# 3V3Buck_Converter.net
KiCad netlist of a schematic drawn in Altium Designer
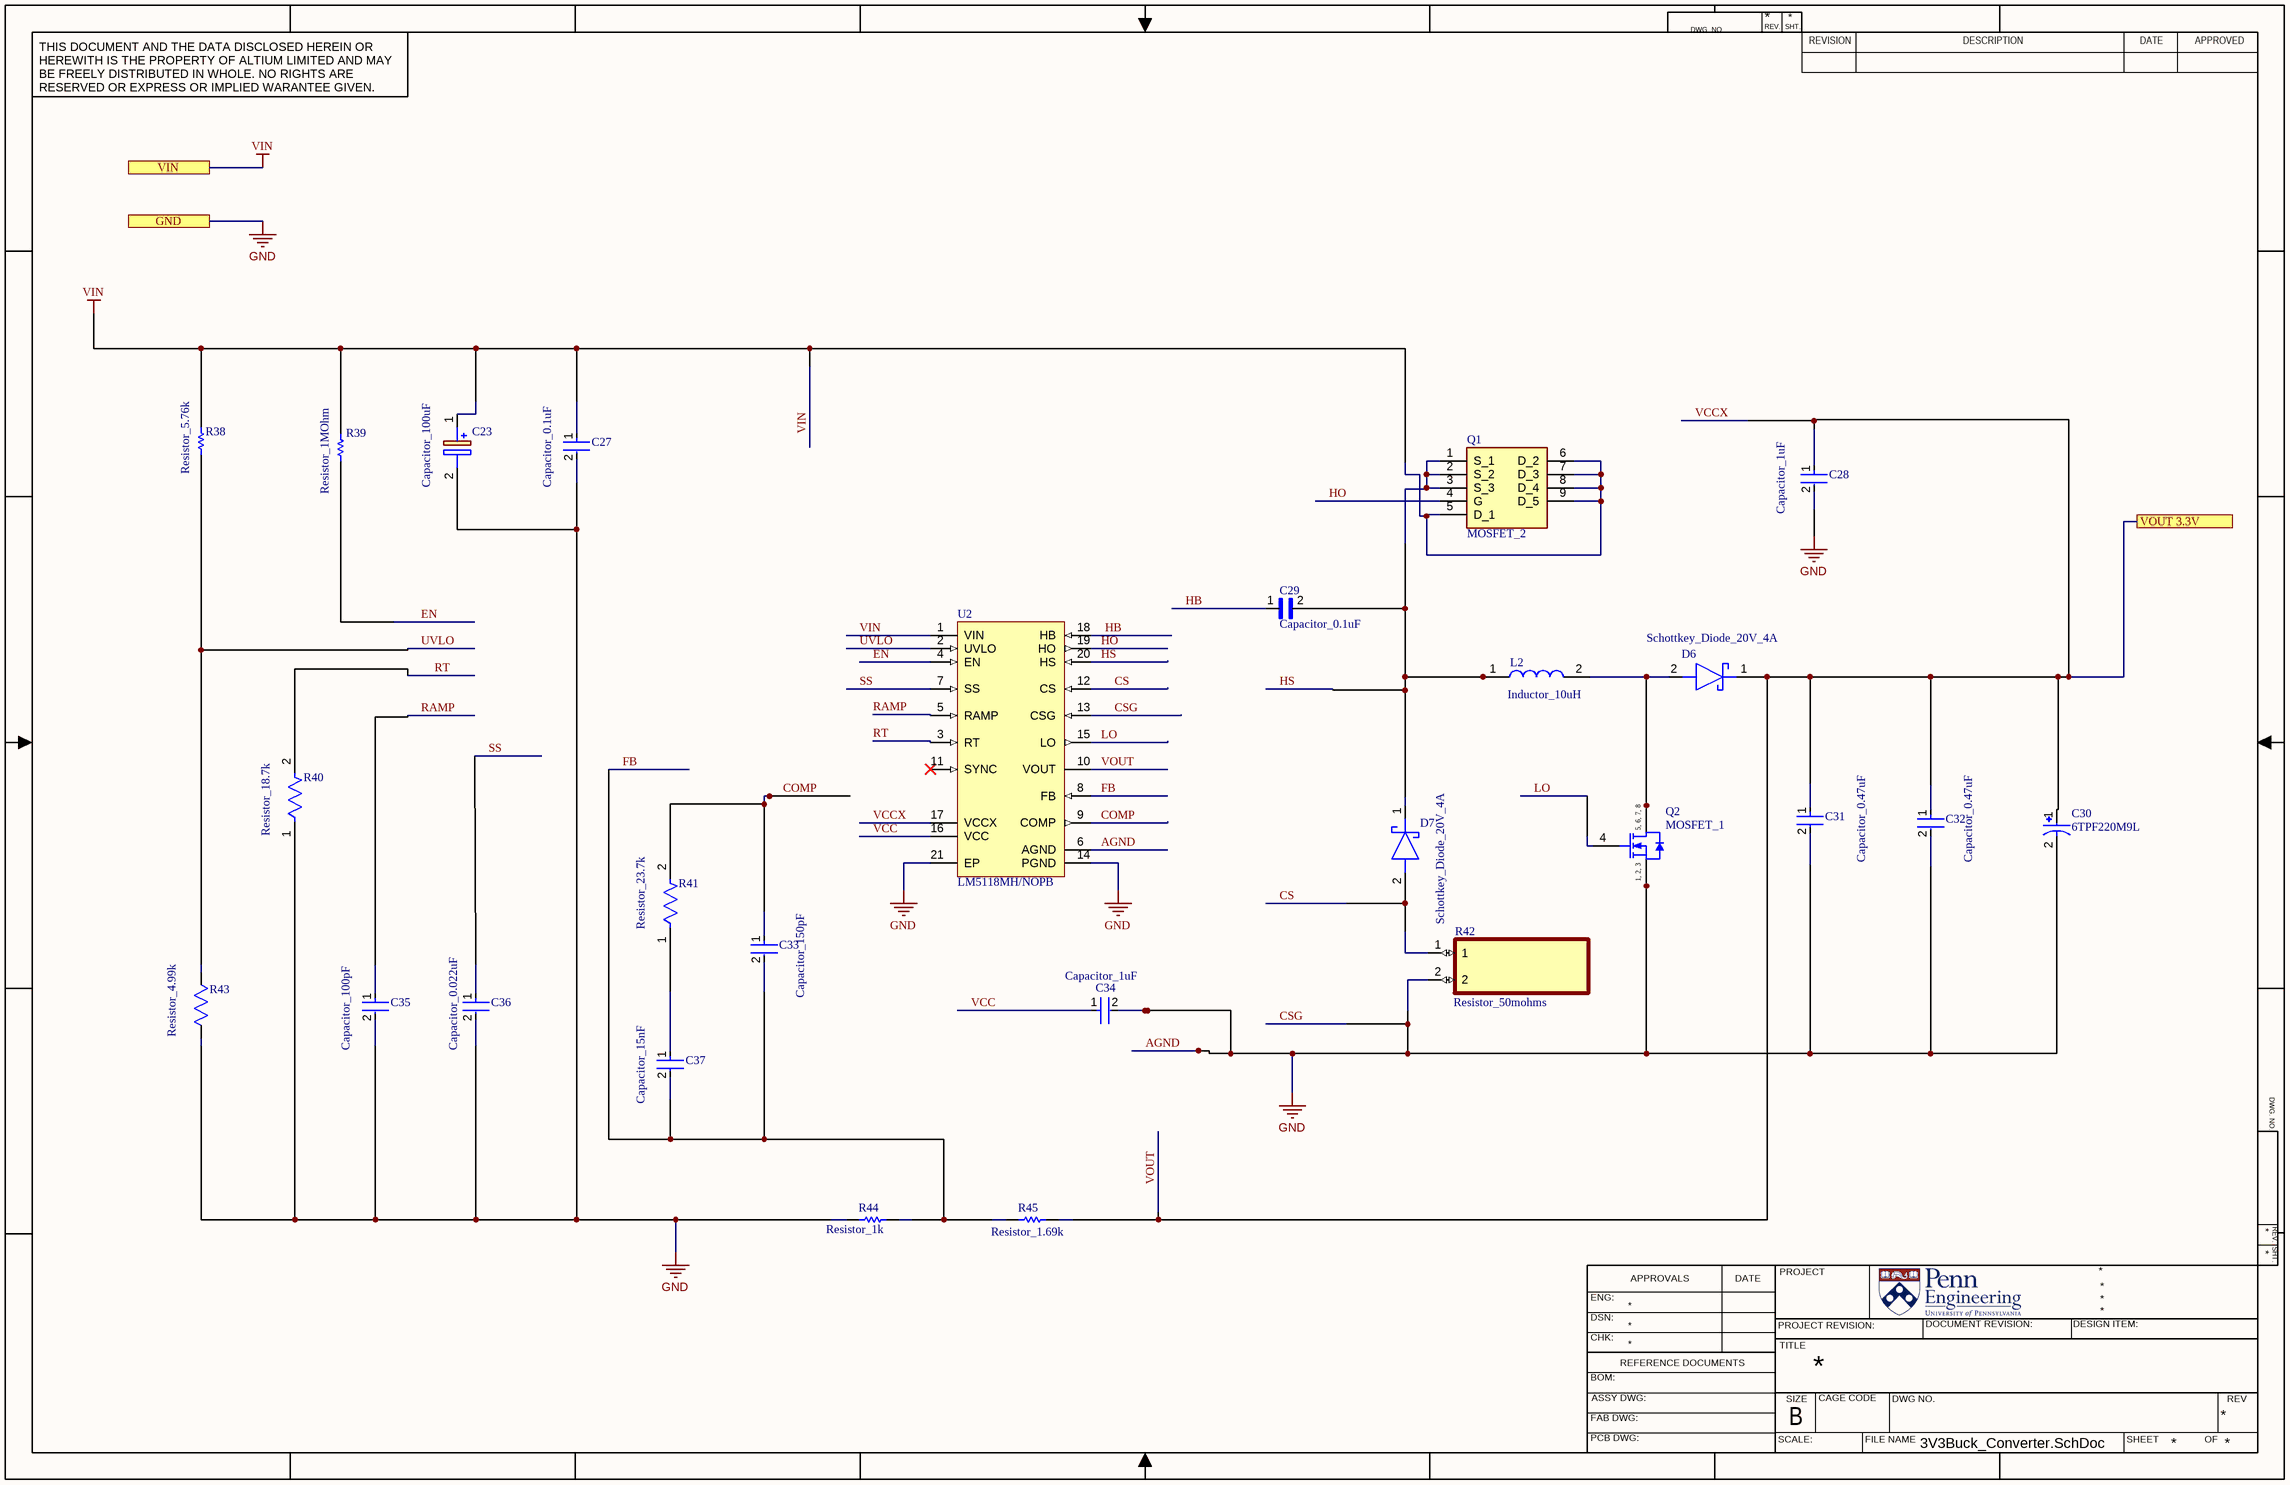
[diagram p0: 3V3Buck_Converter.SchDoc]

(export (version "E")
  (design (tool "Eeschema 10.0.6"))
  (components
    (comp (ref "C23")
      (value "Capacitor_100uF")
      (footprint "Capacitor_100uF")
      (description "Cap Tant Solid 100uF 10V D CASE 20% (7.3 X 4.3 X 2.8mm) Inward L SMD 7343-31 0.1 Ohm 125C T/R")
      (fields
        (field (name "MANUFACTURER") "Vishay Sprague")
        (field (name "MANUFACTURER PART NUMBER") "593D107X0010D2TE3")
      )
      (libsource (lib "Schematic_Lib") (part "Capacitor_100uF"))
    )
    (comp (ref "C27")
      (value "Capacitor_0.1uF")
      (footprint "FP-C0805C-DN-MFG")
      (description "CAP CER 0.1UF 50V X7R 0805")
      (fields (field (name "TOLERANCE") "0.2") (field (name "MANUFACTURER PART NUMBER") "C0805C104M5RACTU"))
      (libsource (lib "Altium Content Vault") (part "b4654b650e69147ec39a6b967a45e02"))
    )
    (comp (ref "C28")
      (value "Capacitor_1uF")
      (footprint "FP-C0603-CG-MFG")
      (description "CAP CER 1UF 10V Y5V 0603")
      (fields (field (name "TOLERANCE") "80%"))
      (libsource (lib "Altium Content Vault") (part "02cd4be3c70576c341d710602a673aa"))
    )
    (comp (ref "C29")
      (value "Capacitor_0.1uF")
      (footprint "Capacitor_0.1uF")
      (description "Cap Ceramic 0.1uF 25V X7R 5% SMD 0805 FlexiTerm 125°C Paper T/R")
      (fields
        (field (name "MANUFACTURER") "Kyocera AVX")
        (field (name "MANUFACTURER PART NUMBER") "08053C104JAZ2A")
      )
      (libsource (lib "Schematic_Lib") (part "Capacitor_0.1uF"))
    )
    (comp (ref "C30")
      (value "6TPF220M9L")
      (footprint "CAP_6TPF220M9L")
      (fields (field (name "MF") "{'manufacturer': u'Panasonic'}"))
      (libsource (lib "SnapEDA_Library") (part "6TPF220M9L"))
    )
    (comp (ref "C31")
      (value "Capacitor_0.47uF")
      (footprint "FP-GRM15-0_1-MFG")
      (description "CAP CER 0.47UF 10V X5R 0402")
      (fields
        (field (name "MANUFACTURER") "Murata Electronics North America")
        (field (name "MANUFACTURER PART NUMBER") "GRM155R61A474KE15D")
      )
      (libsource (lib "Altium Content Vault") (part "11868f565c42a9108669ba33697ecf6"))
    )
    (comp (ref "C32")
      (value "Capacitor_0.47uF")
      (footprint "FP-GRM15-0_1-MFG")
      (description "CAP CER 0.47UF 10V X5R 0402")
      (fields
        (field (name "MANUFACTURER") "Murata Electronics North America")
        (field (name "MANUFACTURER PART NUMBER") "GRM155R61A474KE15D")
      )
      (libsource (lib "Altium Content Vault") (part "11868f565c42a9108669ba33697ecf6"))
    )
    (comp (ref "C33")
      (value "Capacitor_150pF")
      (footprint "FP-CL21-IPC_B")
      (description "CL21 Series 0805 150pF 50V ±5% Tolerance C0G Multilayer Ceramic Chip Capacitor")
      (fields (field (name "TOLERANCE") "5%") (field (name "VOLTAGE") "50V"))
      (libsource (lib "Altium Content Vault") (part "b4654b650e69147ec39a6b967a45e02"))
    )
    (comp (ref "C34")
      (value "Capacitor_1uF")
      (footprint "FP-C0603-CG-MFG")
      (description "CAP CER 1UF 10V Y5V 0603")
      (fields (field (name "TOLERANCE") "80%"))
      (libsource (lib "Altium Content Vault") (part "02cd4be3c70576c341d710602a673aa"))
    )
    (comp (ref "C35")
      (value "Capacitor_100pF")
      (footprint "FP-CL21-IPC_C")
      (description "CL21 Series 0805 100pF 50V ±5% Tolerance C0G Multilayer Ceramic Chip Capacitor")
      (fields (field (name "VOLTAGE") "50V") (field (name "TOLERANCE") "5%"))
      (libsource (lib "Altium Content Vault") (part "b4654b650e69147ec39a6b967a45e02"))
    )
    (comp (ref "C36")
      (value "Capacitor_0.022uF")
      (footprint "FP-C2012-125-0_2-IPC_C")
      (description "CAP CER 0.022UF 50V C0G 0805")
      (fields (field (name "TOLERANCE") "5%") (field (name "VOLTAGE") "50V"))
      (libsource (lib "Altium Content Vault") (part "b4654b650e69147ec39a6b967a45e02"))
    )
    (comp (ref "C37")
      (value "Capacitor_15nF")
      (footprint "FP-CGA4J-IPC_B")
      (description "Cap Ceramic 15nF 50V C0G 5% Pad SMD 0805 +125°C Automotive T/R")
      (fields (field (name "TOLERANCE") "5%"))
      (libsource (lib "Altium Content Vault") (part "b4654b650e69147ec39a6b967a45e02"))
    )
    (comp (ref "D6")
      (value "Schottkey_Diode_20V_4A")
      (footprint "Schottkey Diode_20V_4A")
      (description "SL42 Series 20 V 2 A Surface Mount Schottky Barrier Rectifier - DO-214AB (SMC)")
      (fields
        (field (name "MANUFACTURER") "ON Semiconductor")
        (field (name "MANUFACTURER PART NUMBER") "MBRS320T3")
      )
      (libsource (lib "Schematic_Lib") (part "Schottkey_Diode_20V_4A"))
    )
    (comp (ref "D7")
      (value "Schottkey_Diode_20V_4A")
      (footprint "Schottkey Diode_20V_4A")
      (description "SL42 Series 20 V 2 A Surface Mount Schottky Barrier Rectifier - DO-214AB (SMC)")
      (fields
        (field (name "MANUFACTURER") "ON Semiconductor")
        (field (name "MANUFACTURER PART NUMBER") "MBRS320T3")
      )
      (libsource (lib "Schematic_Lib") (part "Schottkey_Diode_20V_4A"))
    )
    (comp (ref "L2")
      (value "Inductor_10uH")
      (footprint "Inductor_10uH")
      (description "Inductor Power Semi-Shielded Wirewound 10uH 20% 100KHz 17Q-Factor Ferrite 2.5A 58.6mOhm DCR T/R")
      (fields (field (name "MANUFACTURER") "Bourns") (field (name "MANUFACTURER PART NUMBER") "SRN6045-100M"))
      (libsource (lib "Schematic_Lib") (part "Inductor_10uH"))
    )
    (comp (ref "Q1")
      (value "MOSFET_2")
      (footprint "MOSFET_2")
      (description "25-V, N channel NexFET™ power MOSFET, single SON 5 mm x 6 mm, 5.5 mOhm 8-VSONP -55 to 150")
      (fields
        (field (name "MANUFACTURER") "Texas Instruments")
        (field (name "MANUFACTURER PART NUMBER") "CSD16342Q5A")
      )
      (libsource (lib "Schematic_Lib") (part "MOSFET_2"))
    )
    (comp (ref "Q2")
      (value "MOSFET_1")
      (footprint "INF-PG-TDSON-8-1_V")
      (fields (field (name "PARTNUMBER") "BSC046N02KS G") (field (name "MANUFACTURER") "Infineon"))
      (libsource (lib "Altium Content Vault") (part "INF-NEMOS-SSSGDDDD-8"))
    )
    (comp (ref "R38")
      (value "Resistor_5.76k")
      (footprint "RESC1608X55X25ML10T15")
      (description "RES 5.76K OHM 1% 1/10W 0603")
      (fields (field (name "PART NUMBER") "RC0603FR-075K76L") (field (name "MANUFACTURER") "Yageo"))
      (libsource (lib "Altium Content Vault") (part "RES"))
    )
    (comp (ref "R39")
      (value "Resistor_1MOhm")
      (footprint "RESC1608X55X25LL10T15")
      (description "Chip Resistor, 1 MOhm, +/- 1%, 100 mW, -55 to 155 degC, 0603 (1608 Metric), RoHS, Tape and Reel")
      (fields (field (name "TOLERANCE") "20%"))
      (libsource (lib "Altium Content Vault") (part "RES-2"))
    )
    (comp (ref "R40")
      (value "Resistor_18.7k")
      (footprint "FP-AC0402-MFG")
      (description "RES SMD 18.7K OHM 1% 1/16W 0402")
      (fields
        (field (name "OCTOPART") "https://octopart.com/ac0402fr-0718k7l-yageo-71366607")
        (field (name "MANUFACTURER") "Yageo")
      )
      (libsource (lib "Altium Content Vault") (part "1029c3af85768c4190bb7ad29bc67b5"))
    )
    (comp (ref "R41")
      (value "Resistor_23.7k")
      (footprint "FP-AC0402-MFG")
      (description "RES SMD 23.7K OHM 1% 1/16W 0402")
      (fields
        (field (name "OCTOPART") "https://octopart.com/ac0402fr-0723k7l-yageo-71366670")
        (field (name "MANUFACTURER PART NUMBER") "AC0402FR-0723K7L")
      )
      (libsource (lib "Altium Content Vault") (part "1029c3af85768c4190bb7ad29bc67b5"))
    )
    (comp (ref "R42")
      (value "Resistor_50mohms")
      (footprint "Resistor_50mohms")
      (description "Res Thick Film 0805 50m Ohm 1% 1/4W ±100ppm/°C Molded SMD T/R")
      (fields
        (field (name "MANUFACTURER") "Bourns")
        (field (name "MANUFACTURER PART NUMBER") "CRM0805-FW-R050ELF")
      )
      (libsource (lib "Schematic_Lib") (part "Resistor_50mohms"))
    )
    (comp (ref "R43")
      (value "Resistor_4.99k")
      (footprint "Resistor_4.99k")
      (description "Res General Purpose Thick Film 0603 4.99k Ohm 1% 1/10W ±100ppm/°C Molded Paper T/R")
      (fields
        (field (name "MANUFACTURER") "Yageo")
        (field (name "MANUFACTURER PART NUMBER") "RC0603FR-074K99L")
      )
      (libsource (lib "Schematic_Lib") (part "Resistor_4.99k"))
    )
    (comp (ref "R44")
      (value "Resistor_1k")
      (footprint "RESC1608X55X25NL10T15")
      (description "Chip Resistor, 1 KOhm, +/-1%, 0.1 W, -55 to 155 degC, 0603 (1608 Metric), RoHS, Tape and Reel")
      (fields (field (name "MANUFACTURER") "Yageo"))
      (libsource (lib "Altium Content Vault") (part "RES-2"))
    )
    (comp (ref "R45")
      (value "Resistor_1.69k")
      (footprint "RESC1609X50X30ML10T20")
      (description "RES SMD 1.69K OHM 1% 1/10W 0603")
      (fields (field (name "MANUFACTURER") "Vishay Dale") (field (name "PART NUMBER") "CRCW06031K69FKEA"))
      (libsource (lib "Altium Content Vault") (part "RES"))
    )
    (comp (ref "U2")
      (value "LM5118MH/NOPB")
      (footprint "MXA20A_L")
      (description "Wide Voltage Range Buck-Boost Controller, 20-pin TSSOP-EP, Pb-Free")
      (fields (field (name "MANUFACTURER") "National Semiconductor"))
      (libsource (lib "Altium Content Vault") (part "PM-REG-LM5118-21"))
    )
  )
  (nets
    (net (code "1") (name "/COMP") (class "Default")
      (node (ref "C33") (pin "1") (pinfunction "1_1") (pintype "passive"))
      (node (ref "R41") (pin "2") (pinfunction "2_2") (pintype "passive"))
      (node (ref "U2") (pin "9") (pinfunction "COMP_9") (pintype "output"))
    )
    (net (code "2") (name "/CS") (class "Default")
      (node (ref "D7") (pin "2") (pinfunction "A_2") (pintype "passive"))
      (node (ref "R42") (pin "1") (pinfunction "1_1") (pintype "bidirectional"))
      (node (ref "U2") (pin "12") (pinfunction "CS_12") (pintype "input"))
    )
    (net (code "3") (name "/EN") (class "Default")
      (node (ref "R39") (pin "1") (pinfunction "1_1") (pintype "passive"))
      (node (ref "U2") (pin "4") (pinfunction "EN_4") (pintype "input"))
    )
    (net (code "4") (name "/FB") (class "Default")
      (node (ref "C33") (pin "2") (pinfunction "2_2") (pintype "passive"))
      (node (ref "C37") (pin "2") (pinfunction "2_2") (pintype "passive"))
      (node (ref "R44") (pin "2") (pinfunction "2_2") (pintype "passive"))
      (node (ref "R45") (pin "1") (pinfunction "1_1") (pintype "passive"))
      (node (ref "U2") (pin "8") (pinfunction "FB_8") (pintype "input"))
    )
    (net (code "5") (name "/HB") (class "Default")
      (node (ref "C29") (pin "1") (pinfunction "1_1") (pintype "passive"))
      (node (ref "U2") (pin "18") (pinfunction "HB_18") (pintype "input"))
    )
    (net (code "6") (name "/HO") (class "Default")
      (node (ref "Q1") (pin "4") (pinfunction "G_4") (pintype "passive"))
      (node (ref "U2") (pin "19") (pinfunction "HO_19") (pintype "output"))
    )
    (net (code "7") (name "/HS") (class "Default")
      (node (ref "C29") (pin "2") (pinfunction "2_2") (pintype "passive"))
      (node (ref "D7") (pin "1") (pinfunction "K_1") (pintype "passive"))
      (node (ref "L2") (pin "1") (pinfunction "1_1") (pintype "passive"))
      (node (ref "Q1") (pin "1") (pinfunction "S_1_1") (pintype "passive"))
      (node (ref "Q1") (pin "2") (pinfunction "S_2_2") (pintype "passive"))
      (node (ref "Q1") (pin "3") (pinfunction "S_3_3") (pintype "passive"))
      (node (ref "U2") (pin "20") (pinfunction "HS_20") (pintype "input"))
    )
    (net (code "8") (name "/LO") (class "Default")
      (node (ref "Q2") (pin "4") (pinfunction "GATE_4") (pintype "passive"))
      (node (ref "U2") (pin "15") (pinfunction "LO_15") (pintype "output"))
    )
    (net (code "9") (name "/RAMP") (class "Default")
      (node (ref "C35") (pin "1") (pinfunction "1_1") (pintype "passive"))
      (node (ref "U2") (pin "5") (pinfunction "RAMP_5") (pintype "input"))
    )
    (net (code "10") (name "/RT") (class "Default")
      (node (ref "R40") (pin "2") (pinfunction "2_2") (pintype "passive"))
      (node (ref "U2") (pin "3") (pinfunction "RT_3") (pintype "input"))
    )
    (net (code "11") (name "/SS") (class "Default")
      (node (ref "C36") (pin "1") (pinfunction "1_1") (pintype "passive"))
      (node (ref "U2") (pin "7") (pinfunction "SS_7") (pintype "input"))
    )
    (net (code "12") (name "/UVLO") (class "Default")
      (node (ref "R38") (pin "1") (pinfunction "1_1") (pintype "passive"))
      (node (ref "R43") (pin "1") (pinfunction "R1_1") (pintype "passive"))
      (node (ref "U2") (pin "2") (pinfunction "UVLO_2") (pintype "input"))
    )
    (net (code "13") (name "/VCC") (class "Default")
      (node (ref "C34") (pin "1") (pinfunction "1_1") (pintype "passive"))
      (node (ref "U2") (pin "16") (pinfunction "VCC_16") (pintype "power_in"))
    )
    (net (code "14") (name "/VCCX") (class "Default")
      (node (ref "C28") (pin "1") (pinfunction "1_1") (pintype "passive"))
      (node (ref "C30") (pin "1") (pinfunction "1_1") (pintype "passive"))
      (node (ref "C31") (pin "1") (pinfunction "1_1") (pintype "passive"))
      (node (ref "C32") (pin "1") (pinfunction "1_1") (pintype "passive"))
      (node (ref "D6") (pin "1") (pinfunction "K_1") (pintype "passive"))
      (node (ref "R45") (pin "2") (pinfunction "2_2") (pintype "passive"))
      (node (ref "U2") (pin "10") (pinfunction "VOUT_10") (pintype "power_in"))
      (node (ref "U2") (pin "17") (pinfunction "VCCX_17") (pintype "power_in"))
    )
    (net (code "15") (name "GND") (class "Default")
      (node (ref "C23") (pin "2") (pinfunction "-_2") (pintype "passive"))
      (node (ref "C27") (pin "2") (pinfunction "2_2") (pintype "passive"))
      (node (ref "C28") (pin "2") (pinfunction "2_2") (pintype "passive"))
      (node (ref "C30") (pin "2") (pinfunction "2_2") (pintype "passive"))
      (node (ref "C31") (pin "2") (pinfunction "2_2") (pintype "passive"))
      (node (ref "C32") (pin "2") (pinfunction "2_2") (pintype "passive"))
      (node (ref "C34") (pin "2") (pinfunction "2_2") (pintype "passive"))
      (node (ref "C35") (pin "2") (pinfunction "2_2") (pintype "passive"))
      (node (ref "C36") (pin "2") (pinfunction "2_2") (pintype "passive"))
      (node (ref "Q2") (pin "1") (pinfunction "SOURCE_1") (pintype "passive"))
      (node (ref "Q2") (pin "2") (pinfunction "SOURCE_2") (pintype "passive"))
      (node (ref "Q2") (pin "3") (pinfunction "SOURCE_3") (pintype "passive"))
      (node (ref "R40") (pin "1") (pinfunction "1_1") (pintype "passive"))
      (node (ref "R42") (pin "2") (pinfunction "2_2") (pintype "bidirectional"))
      (node (ref "R43") (pin "2") (pinfunction "R2_2") (pintype "passive"))
      (node (ref "R44") (pin "1") (pinfunction "1_1") (pintype "passive"))
      (node (ref "U2") (pin "13") (pinfunction "CSG_13") (pintype "input"))
      (node (ref "U2") (pin "14") (pinfunction "PGND_14") (pintype "power_in"))
      (node (ref "U2") (pin "21") (pinfunction "EP_21") (pintype "power_in"))
      (node (ref "U2") (pin "6") (pinfunction "AGND_6") (pintype "power_in"))
    )
    (net (code "16") (name "Net-(C37-Pad1)") (class "Default")
      (node (ref "C37") (pin "1") (pinfunction "1_1") (pintype "passive"))
      (node (ref "R41") (pin "1") (pinfunction "1_1") (pintype "passive"))
    )
    (net (code "17") (name "Net-(D6-A)") (class "Default")
      (node (ref "D6") (pin "2") (pinfunction "A_2") (pintype "passive"))
      (node (ref "L2") (pin "2") (pinfunction "2_2") (pintype "passive"))
      (node (ref "Q2") (pin "5") (pinfunction "DRAIN_5") (pintype "passive"))
      (node (ref "Q2") (pin "6") (pinfunction "DRAIN_6") (pintype "passive"))
      (node (ref "Q2") (pin "7") (pinfunction "DRAIN_7") (pintype "passive"))
      (node (ref "Q2") (pin "8") (pinfunction "DRAIN_8") (pintype "passive"))
    )
    (net (code "18") (name "VIN") (class "Default")
      (node (ref "C23") (pin "1") (pinfunction "+_1") (pintype "passive"))
      (node (ref "C27") (pin "1") (pinfunction "1_1") (pintype "passive"))
      (node (ref "Q1") (pin "5") (pinfunction "D_1_5") (pintype "passive"))
      (node (ref "Q1") (pin "6") (pinfunction "D_2_6") (pintype "passive"))
      (node (ref "Q1") (pin "7") (pinfunction "D_3_7") (pintype "passive"))
      (node (ref "Q1") (pin "8") (pinfunction "D_4_8") (pintype "passive"))
      (node (ref "Q1") (pin "9") (pinfunction "D_5_9") (pintype "passive"))
      (node (ref "R38") (pin "2") (pinfunction "2_2") (pintype "passive"))
      (node (ref "R39") (pin "2") (pinfunction "2_2") (pintype "passive"))
      (node (ref "U2") (pin "1") (pinfunction "VIN_1") (pintype "power_in"))
    )
    (net (code "19") (name "unconnected-(U2-SYNC-Pad11)") (class "Default")
      (node (ref "U2") (pin "11") (pinfunction "SYNC_11") (pintype "input+no_connect"))
    )
  )
)
